# flight_computer.net
KiCad netlist of a schematic drawn in EAGLE
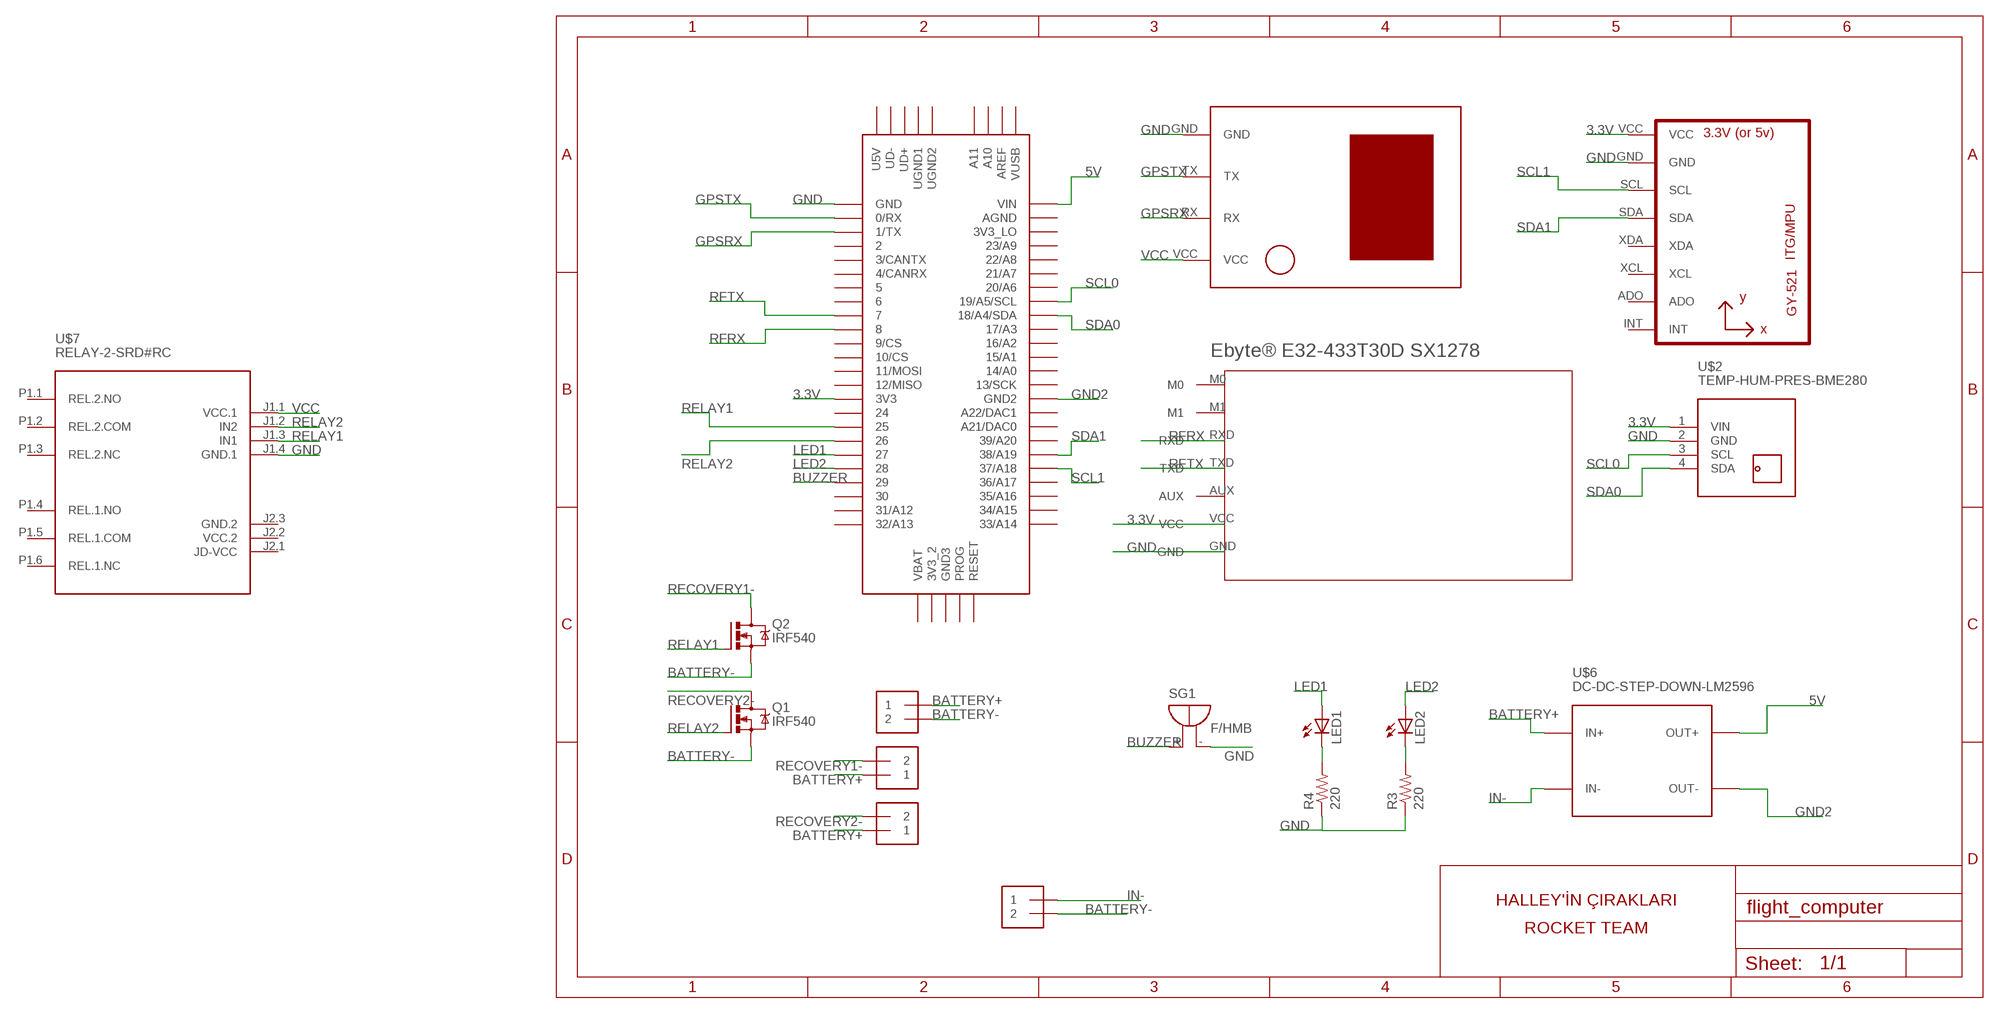
[diagram p0: schematic, sheet 1]

(export (version "E")
  (design (tool "Eeschema 10.0.6"))
  (components
    (comp (ref "J1")
      (value "1X2-3.5MM")
      (footprint "eagle-import:1X2-3.5MM")
      (libsource (lib "eagle-import") (part "1X2-3.5MM"))
    )
    (comp (ref "J2")
      (value "1X2-3.5MM")
      (footprint "eagle-import:1X2-3.5MM")
      (libsource (lib "eagle-import") (part "1X2-3.5MM"))
    )
    (comp (ref "J3")
      (value "1X2-3.5MM")
      (footprint "eagle-import:1X2-3.5MM")
      (libsource (lib "eagle-import") (part "1X2-3.5MM"))
    )
    (comp (ref "J4")
      (value "1X2-3.5MM")
      (footprint "eagle-import:1X2-3.5MM")
      (libsource (lib "eagle-import") (part "1X2-3.5MM"))
    )
    (comp (ref "LED1")
      (value "LED5MM")
      (footprint "eagle-import:LED5MM")
      (libsource (lib "eagle-import") (part "LED5MM"))
    )
    (comp (ref "LED2")
      (value "LED5MM")
      (footprint "eagle-import:LED5MM")
      (libsource (lib "eagle-import") (part "LED5MM"))
    )
    (comp (ref "Q1")
      (value "IRF540")
      (footprint "eagle-import:TO220BV")
      (fields (field (name "MANUFACTURER") "Infineon Technologies") (field (name "MPN") "IRF540NPBF"))
      (libsource (lib "eagle-import") (part "NMOSFET_-TO220IRF540"))
    )
    (comp (ref "Q2")
      (value "IRF540")
      (footprint "eagle-import:TO220BV")
      (fields (field (name "MANUFACTURER") "Infineon Technologies") (field (name "MPN") "IRF540NPBF"))
      (libsource (lib "eagle-import") (part "NMOSFET_-TO220IRF540"))
    )
    (comp (ref "R3")
      (value "220")
      (footprint "eagle-import:0204_7")
      (libsource (lib "eagle-import") (part "R-US_0204/7"))
    )
    (comp (ref "R4")
      (value "220")
      (footprint "eagle-import:0204_7")
      (libsource (lib "eagle-import") (part "R-US_0204/7"))
    )
    (comp (ref "SG1")
      (value "F/HMB")
      (footprint "eagle-import:F_HMB")
      (libsource (lib "eagle-import") (part "F/HMB"))
    )
    (comp (ref "U$1")
      (value "U-BLOX-NEO6V2")
      (footprint "eagle-import:U-BLOX-NEO6V2")
      (libsource (lib "eagle-import") (part "U-BLOX-NEO6V2"))
    )
    (comp (ref "U$2")
      (value "TEMP-HUM-PRES-BME280")
      (footprint "eagle-import:TEMP-HUM-PRES-BME280")
      (libsource (lib "eagle-import") (part "TEMP-HUM-PRES-BME280"))
    )
    (comp (ref "U$3")
      (value "TEENSY_3.5/3.6")
      (footprint "eagle-import:TEENSY_3.5_3.6")
      (libsource (lib "eagle-import") (part "TEENSY_3.5/3.6"))
    )
    (comp (ref "U$4")
      (value "EBYTE®E32-433T30DSX1278")
      (footprint "eagle-import:E32-433T30D")
      (libsource (lib "eagle-import") (part "EBYTE®E32-433T30DSX1278"))
    )
    (comp (ref "U$6")
      (value "DC-DC-STEP-DOWN-LM2596")
      (footprint "eagle-import:DC-DC-STEP-DOWN-LM2596")
      (libsource (lib "eagle-import") (part "DC-DC-STEP-DOWN-LM2596"))
    )
    (comp (ref "U$7")
      (value "RELAY-2-SRD#RC")
      (footprint "eagle-import:RELAY-2-SRD#RC")
      (libsource (lib "eagle-import") (part "RELAY-2-SRD#RC"))
    )
    (comp (ref "U1")
      (value "GY-521MPU6050")
      (footprint "eagle-import:GY-521")
      (libsource (lib "eagle-import") (part "GY-521MPU6050"))
    )
  )
  (nets
    (net (code "1") (name "/3.3V") (class "Default")
      (node (ref "U$2") (pin "1") (pinfunction "VIN_1") (pintype "power_in"))
      (node (ref "U$3") (pin "3V3") (pinfunction "3V3_3V3") (pintype "bidirectional"))
      (node (ref "U$4") (pin "VCC") (pinfunction "VCC_VCC") (pintype "bidirectional"))
      (node (ref "U1") (pin "VCC") (pinfunction "VCC_VCC") (pintype "bidirectional"))
    )
    (net (code "2") (name "/5V") (class "Default")
      (node (ref "U$3") (pin "VIN") (pinfunction "VIN_VIN") (pintype "bidirectional"))
      (node (ref "U$6") (pin "OUT+") (pinfunction "OUT+_OUT+") (pintype "bidirectional"))
    )
    (net (code "3") (name "/BATTERY+") (class "Default")
      (node (ref "J1") (pin "1") (pinfunction "1_1") (pintype "passive"))
      (node (ref "J2") (pin "1") (pinfunction "1_1") (pintype "passive"))
      (node (ref "J3") (pin "1") (pinfunction "1_1") (pintype "passive"))
      (node (ref "U$6") (pin "IN+") (pinfunction "IN+_IN+") (pintype "bidirectional"))
    )
    (net (code "4") (name "/BATTERY-") (class "Default")
      (node (ref "J1") (pin "2") (pinfunction "2_2") (pintype "passive"))
      (node (ref "J4") (pin "2") (pinfunction "2_2") (pintype "passive"))
      (node (ref "Q1") (pin "S") (pinfunction "S_S") (pintype "passive"))
      (node (ref "Q2") (pin "S") (pinfunction "S_S") (pintype "passive"))
    )
    (net (code "5") (name "/BUZZER") (class "Default")
      (node (ref "SG1") (pin "+") (pinfunction "+_+") (pintype "passive"))
      (node (ref "U$3") (pin "29") (pinfunction "29_29") (pintype "bidirectional"))
    )
    (net (code "6") (name "/GND") (class "Default")
      (node (ref "R3") (pin "1") (pinfunction "1_1") (pintype "passive"))
      (node (ref "R4") (pin "1") (pinfunction "1_1") (pintype "passive"))
      (node (ref "SG1") (pin "-") (pinfunction "-_-") (pintype "passive"))
      (node (ref "U$1") (pin "GND") (pinfunction "GND_GND") (pintype "bidirectional"))
      (node (ref "U$2") (pin "2") (pinfunction "GND_2") (pintype "power_in"))
      (node (ref "U$3") (pin "GND") (pinfunction "GND_GND") (pintype "bidirectional"))
      (node (ref "U$4") (pin "GND") (pinfunction "GND_GND") (pintype "bidirectional"))
      (node (ref "U$7") (pin "J1.4") (pinfunction "GND.1_J1.4") (pintype "power_in"))
      (node (ref "U1") (pin "GND") (pinfunction "GND_GND") (pintype "bidirectional"))
    )
    (net (code "7") (name "/GND.2") (class "Default")
      (node (ref "U$7") (pin "J2.3") (pinfunction "GND.2_J2.3") (pintype "power_in"))
    )
    (net (code "8") (name "/GND2") (class "Default")
      (node (ref "U$3") (pin "GND2") (pinfunction "GND2_GND2") (pintype "bidirectional"))
      (node (ref "U$6") (pin "OUT-") (pinfunction "OUT-_OUT-") (pintype "bidirectional"))
    )
    (net (code "9") (name "/GPSRX") (class "Default")
      (node (ref "U$1") (pin "RX") (pinfunction "RX_RX") (pintype "bidirectional"))
      (node (ref "U$3") (pin "1/TX") (pinfunction "1/TX_1/TX") (pintype "bidirectional"))
    )
    (net (code "10") (name "/GPSTX") (class "Default")
      (node (ref "U$1") (pin "TX") (pinfunction "TX_TX") (pintype "bidirectional"))
      (node (ref "U$3") (pin "0/RX") (pinfunction "0/RX_0/RX") (pintype "bidirectional"))
    )
    (net (code "11") (name "/IN-") (class "Default")
      (node (ref "J4") (pin "1") (pinfunction "1_1") (pintype "passive"))
      (node (ref "U$6") (pin "IN-") (pinfunction "IN-_IN-") (pintype "bidirectional"))
    )
    (net (code "12") (name "/LED1") (class "Default")
      (node (ref "LED1") (pin "A") (pinfunction "A_A") (pintype "passive"))
      (node (ref "U$3") (pin "27") (pinfunction "27_27") (pintype "bidirectional"))
    )
    (net (code "13") (name "/LED2") (class "Default")
      (node (ref "LED2") (pin "A") (pinfunction "A_A") (pintype "passive"))
      (node (ref "U$3") (pin "28") (pinfunction "28_28") (pintype "bidirectional"))
    )
    (net (code "14") (name "/RECOVERY1-") (class "Default")
      (node (ref "J2") (pin "2") (pinfunction "2_2") (pintype "passive"))
      (node (ref "Q2") (pin "D") (pinfunction "D_D") (pintype "passive"))
    )
    (net (code "15") (name "/RECOVERY2-") (class "Default")
      (node (ref "J3") (pin "2") (pinfunction "2_2") (pintype "passive"))
      (node (ref "Q1") (pin "D") (pinfunction "D_D") (pintype "passive"))
    )
    (net (code "16") (name "/RELAY1") (class "Default")
      (node (ref "Q2") (pin "G") (pinfunction "G_G") (pintype "passive"))
      (node (ref "U$3") (pin "25") (pinfunction "25_25") (pintype "bidirectional"))
      (node (ref "U$7") (pin "J1.3") (pinfunction "IN1_J1.3") (pintype "bidirectional"))
    )
    (net (code "17") (name "/RELAY2") (class "Default")
      (node (ref "Q1") (pin "G") (pinfunction "G_G") (pintype "passive"))
      (node (ref "U$3") (pin "26") (pinfunction "26_26") (pintype "bidirectional"))
      (node (ref "U$7") (pin "J1.2") (pinfunction "IN2_J1.2") (pintype "bidirectional"))
    )
    (net (code "18") (name "/RFRX") (class "Default")
      (node (ref "U$3") (pin "8") (pinfunction "8_8") (pintype "bidirectional"))
      (node (ref "U$4") (pin "RXD") (pinfunction "RXD_RXD") (pintype "bidirectional"))
    )
    (net (code "19") (name "/RFTX") (class "Default")
      (node (ref "U$3") (pin "7") (pinfunction "7_7") (pintype "bidirectional"))
      (node (ref "U$4") (pin "TXD") (pinfunction "TXD_TXD") (pintype "bidirectional"))
    )
    (net (code "20") (name "/SCL0") (class "Default")
      (node (ref "U$2") (pin "3") (pinfunction "SCL_3") (pintype "bidirectional"))
      (node (ref "U$3") (pin "19/A5/SCL") (pinfunction "19/A5/SCL_19/A5/SCL") (pintype "bidirectional"))
    )
    (net (code "21") (name "/SCL1") (class "Default")
      (node (ref "U$3") (pin "37/A18") (pinfunction "37/A18_37/A18") (pintype "bidirectional"))
      (node (ref "U1") (pin "SCL") (pinfunction "SCL_SCL") (pintype "bidirectional"))
    )
    (net (code "22") (name "/SDA0") (class "Default")
      (node (ref "U$2") (pin "4") (pinfunction "SDA_4") (pintype "bidirectional"))
      (node (ref "U$3") (pin "18/A4/SDA") (pinfunction "18/A4/SDA_18/A4/SDA") (pintype "bidirectional"))
    )
    (net (code "23") (name "/SDA1") (class "Default")
      (node (ref "U$3") (pin "38/A19") (pinfunction "38/A19_38/A19") (pintype "bidirectional"))
      (node (ref "U1") (pin "SDA") (pinfunction "SDA_SDA") (pintype "bidirectional"))
    )
    (net (code "24") (name "/VCC") (class "Default")
      (node (ref "U$1") (pin "VCC") (pinfunction "VCC_VCC") (pintype "bidirectional"))
      (node (ref "U$7") (pin "J1.1") (pinfunction "VCC.1_J1.1") (pintype "power_in"))
    )
    (net (code "25") (name "/VCC.2") (class "Default")
      (node (ref "U$7") (pin "J2.2") (pinfunction "VCC.2_J2.2") (pintype "power_in"))
    )
    (net (code "26") (name "Net-(LED1-C)") (class "Default")
      (node (ref "LED1") (pin "K") (pinfunction "C_K") (pintype "passive"))
      (node (ref "R4") (pin "2") (pinfunction "2_2") (pintype "passive"))
    )
    (net (code "27") (name "Net-(LED2-C)") (class "Default")
      (node (ref "LED2") (pin "K") (pinfunction "C_K") (pintype "passive"))
      (node (ref "R3") (pin "2") (pinfunction "2_2") (pintype "passive"))
    )
    (net (code "28") (name "unconnected-(U$3-A21{slash}DAC0-Pad21{slash}DAC0)") (class "Default")
      (node (ref "U$3") (pin "21/DAC0") (pinfunction "A21/DAC0_21/DAC0") (pintype "bidirectional"))
    )
    (net (code "29") (name "unconnected-(U$3-Pad2)") (class "Default")
      (node (ref "U$3") (pin "2") (pinfunction "2_2") (pintype "bidirectional"))
    )
    (net (code "30") (name "unconnected-(U$3-Pad3V3_2)") (class "Default")
      (node (ref "U$3") (pin "3V3_2") (pinfunction "3V3_2_3V3_2") (pintype "bidirectional"))
    )
    (net (code "31") (name "unconnected-(U$3-Pad3V3_LO)") (class "Default")
      (node (ref "U$3") (pin "3V3_LO") (pinfunction "3V3_LO_3V3_LO") (pintype "bidirectional"))
    )
    (net (code "32") (name "unconnected-(U$3-Pad3{slash}CANTX)") (class "Default")
      (node (ref "U$3") (pin "3/CANTX") (pinfunction "3/CANTX_3/CANTX") (pintype "bidirectional"))
    )
    (net (code "33") (name "unconnected-(U$3-Pad4{slash}CANRX)") (class "Default")
      (node (ref "U$3") (pin "4/CANRX") (pinfunction "4/CANRX_4/CANRX") (pintype "bidirectional"))
    )
    (net (code "34") (name "unconnected-(U$3-Pad5)") (class "Default")
      (node (ref "U$3") (pin "5") (pinfunction "5_5") (pintype "bidirectional"))
    )
    (net (code "35") (name "unconnected-(U$3-Pad6)") (class "Default")
      (node (ref "U$3") (pin "6") (pinfunction "6_6") (pintype "bidirectional"))
    )
    (net (code "36") (name "unconnected-(U$3-Pad9{slash}CS)") (class "Default")
      (node (ref "U$3") (pin "9/CS") (pinfunction "9/CS_9/CS") (pintype "bidirectional"))
    )
    (net (code "37") (name "unconnected-(U$3-Pad10{slash}CS)") (class "Default")
      (node (ref "U$3") (pin "10/CS") (pinfunction "10/CS_10/CS") (pintype "bidirectional"))
    )
    (net (code "38") (name "unconnected-(U$3-Pad11{slash}MOSI)") (class "Default")
      (node (ref "U$3") (pin "11/MOSI") (pinfunction "11/MOSI_11/MOSI") (pintype "bidirectional"))
    )
    (net (code "39") (name "unconnected-(U$3-Pad12{slash}MISO)") (class "Default")
      (node (ref "U$3") (pin "12/MISO") (pinfunction "12/MISO_12/MISO") (pintype "bidirectional"))
    )
    (net (code "40") (name "unconnected-(U$3-Pad13{slash}SCK)") (class "Default")
      (node (ref "U$3") (pin "13/SCK") (pinfunction "13/SCK_13/SCK") (pintype "bidirectional"))
    )
    (net (code "41") (name "unconnected-(U$3-Pad14{slash}A0)") (class "Default")
      (node (ref "U$3") (pin "14/A0") (pinfunction "14/A0_14/A0") (pintype "bidirectional"))
    )
    (net (code "42") (name "unconnected-(U$3-Pad15{slash}A1)") (class "Default")
      (node (ref "U$3") (pin "15/A1") (pinfunction "15/A1_15/A1") (pintype "bidirectional"))
    )
    (net (code "43") (name "unconnected-(U$3-Pad16{slash}A2)") (class "Default")
      (node (ref "U$3") (pin "16/A2") (pinfunction "16/A2_16/A2") (pintype "bidirectional"))
    )
    (net (code "44") (name "unconnected-(U$3-Pad17{slash}A3)") (class "Default")
      (node (ref "U$3") (pin "17/A3") (pinfunction "17/A3_17/A3") (pintype "bidirectional"))
    )
    (net (code "45") (name "unconnected-(U$3-Pad20{slash}A6)") (class "Default")
      (node (ref "U$3") (pin "20/A6") (pinfunction "20/A6_20/A6") (pintype "bidirectional"))
    )
    (net (code "46") (name "unconnected-(U$3-Pad21{slash}A7)") (class "Default")
      (node (ref "U$3") (pin "21/A7") (pinfunction "21/A7_21/A7") (pintype "bidirectional"))
    )
    (net (code "47") (name "unconnected-(U$3-Pad22{slash}A8)") (class "Default")
      (node (ref "U$3") (pin "22/A8") (pinfunction "22/A8_22/A8") (pintype "bidirectional"))
    )
    (net (code "48") (name "unconnected-(U$3-Pad23{slash}A9)") (class "Default")
      (node (ref "U$3") (pin "23/A9") (pinfunction "23/A9_23/A9") (pintype "bidirectional"))
    )
    (net (code "49") (name "unconnected-(U$3-Pad24)") (class "Default")
      (node (ref "U$3") (pin "24") (pinfunction "24_24") (pintype "bidirectional"))
    )
    (net (code "50") (name "unconnected-(U$3-Pad30)") (class "Default")
      (node (ref "U$3") (pin "30") (pinfunction "30_30") (pintype "bidirectional"))
    )
    (net (code "51") (name "unconnected-(U$3-Pad31{slash}A12)") (class "Default")
      (node (ref "U$3") (pin "31/A12") (pinfunction "31/A12_31/A12") (pintype "bidirectional"))
    )
    (net (code "52") (name "unconnected-(U$3-Pad32{slash}A13)") (class "Default")
      (node (ref "U$3") (pin "32/A13") (pinfunction "32/A13_32/A13") (pintype "bidirectional"))
    )
    (net (code "53") (name "unconnected-(U$3-Pad33{slash}A14)") (class "Default")
      (node (ref "U$3") (pin "33/A14") (pinfunction "33/A14_33/A14") (pintype "bidirectional"))
    )
    (net (code "54") (name "unconnected-(U$3-Pad34{slash}A15)") (class "Default")
      (node (ref "U$3") (pin "34/A15") (pinfunction "34/A15_34/A15") (pintype "bidirectional"))
    )
    (net (code "55") (name "unconnected-(U$3-Pad35{slash}A16)") (class "Default")
      (node (ref "U$3") (pin "35/A16") (pinfunction "35/A16_35/A16") (pintype "bidirectional"))
    )
    (net (code "56") (name "unconnected-(U$3-Pad36{slash}A17)") (class "Default")
      (node (ref "U$3") (pin "36/A17") (pinfunction "36/A17_36/A17") (pintype "bidirectional"))
    )
    (net (code "57") (name "unconnected-(U$3-Pad39{slash}A20)") (class "Default")
      (node (ref "U$3") (pin "39/A20") (pinfunction "39/A20_39/A20") (pintype "bidirectional"))
    )
    (net (code "58") (name "unconnected-(U$3-PadA10)") (class "Default")
      (node (ref "U$3") (pin "A10") (pinfunction "A10_A10") (pintype "bidirectional"))
    )
    (net (code "59") (name "unconnected-(U$3-PadA11)") (class "Default")
      (node (ref "U$3") (pin "A11") (pinfunction "A11_A11") (pintype "bidirectional"))
    )
    (net (code "60") (name "unconnected-(U$3-PadA22{slash}DAC1)") (class "Default")
      (node (ref "U$3") (pin "A22/DAC1") (pinfunction "A22/DAC1_A22/DAC1") (pintype "bidirectional"))
    )
    (net (code "61") (name "unconnected-(U$3-PadAGND)") (class "Default")
      (node (ref "U$3") (pin "AGND") (pinfunction "AGND_AGND") (pintype "bidirectional"))
    )
    (net (code "62") (name "unconnected-(U$3-PadAREF)") (class "Default")
      (node (ref "U$3") (pin "AREF") (pinfunction "AREF_AREF") (pintype "bidirectional"))
    )
    (net (code "63") (name "unconnected-(U$3-PadGND3)") (class "Default")
      (node (ref "U$3") (pin "GND3") (pinfunction "GND3_GND3") (pintype "bidirectional"))
    )
    (net (code "64") (name "unconnected-(U$3-PadPROG)") (class "Default")
      (node (ref "U$3") (pin "PROG") (pinfunction "PROG_PROG") (pintype "bidirectional"))
    )
    (net (code "65") (name "unconnected-(U$3-PadRESET)") (class "Default")
      (node (ref "U$3") (pin "RESET") (pinfunction "RESET_RESET") (pintype "bidirectional"))
    )
    (net (code "66") (name "unconnected-(U$3-PadU5V)") (class "Default")
      (node (ref "U$3") (pin "U5V") (pinfunction "U5V_U5V") (pintype "bidirectional"))
    )
    (net (code "67") (name "unconnected-(U$3-PadUD+)") (class "Default")
      (node (ref "U$3") (pin "UD+") (pinfunction "UD+_UD+") (pintype "bidirectional"))
    )
    (net (code "68") (name "unconnected-(U$3-PadUD-)") (class "Default")
      (node (ref "U$3") (pin "UD-") (pinfunction "UD-_UD-") (pintype "bidirectional"))
    )
    (net (code "69") (name "unconnected-(U$3-PadUGND1)") (class "Default")
      (node (ref "U$3") (pin "UGND1") (pinfunction "UGND1_UGND1") (pintype "bidirectional"))
    )
    (net (code "70") (name "unconnected-(U$3-PadUGND2)") (class "Default")
      (node (ref "U$3") (pin "UGND2") (pinfunction "UGND2_UGND2") (pintype "bidirectional"))
    )
    (net (code "71") (name "unconnected-(U$3-PadVBAT)") (class "Default")
      (node (ref "U$3") (pin "VBAT") (pinfunction "VBAT_VBAT") (pintype "bidirectional"))
    )
    (net (code "72") (name "unconnected-(U$3-PadVUSB)") (class "Default")
      (node (ref "U$3") (pin "VUSB") (pinfunction "VUSB_VUSB") (pintype "bidirectional"))
    )
    (net (code "73") (name "unconnected-(U$4-PadAUX)") (class "Default")
      (node (ref "U$4") (pin "AUX") (pinfunction "AUX_AUX") (pintype "bidirectional"))
    )
    (net (code "74") (name "unconnected-(U$4-PadM0)") (class "Default")
      (node (ref "U$4") (pin "M0") (pinfunction "M0_M0") (pintype "bidirectional"))
    )
    (net (code "75") (name "unconnected-(U$4-PadM1)") (class "Default")
      (node (ref "U$4") (pin "M1") (pinfunction "M1_M1") (pintype "bidirectional"))
    )
    (net (code "76") (name "unconnected-(U$7-JD-VCC-PadJ2.1)") (class "Default")
      (node (ref "U$7") (pin "J2.1") (pinfunction "JD-VCC_J2.1") (pintype "bidirectional"))
    )
    (net (code "77") (name "unconnected-(U$7-REL.1.COM-PadP1.5)") (class "Default")
      (node (ref "U$7") (pin "P1.5") (pinfunction "REL.1.COM_P1.5") (pintype "bidirectional"))
    )
    (net (code "78") (name "unconnected-(U$7-REL.1.NC-PadP1.6)") (class "Default")
      (node (ref "U$7") (pin "P1.6") (pinfunction "REL.1.NC_P1.6") (pintype "bidirectional"))
    )
    (net (code "79") (name "unconnected-(U$7-REL.1.NO-PadP1.4)") (class "Default")
      (node (ref "U$7") (pin "P1.4") (pinfunction "REL.1.NO_P1.4") (pintype "bidirectional"))
    )
    (net (code "80") (name "unconnected-(U$7-REL.2.COM-PadP1.2)") (class "Default")
      (node (ref "U$7") (pin "P1.2") (pinfunction "REL.2.COM_P1.2") (pintype "bidirectional"))
    )
    (net (code "81") (name "unconnected-(U$7-REL.2.NC-PadP1.3)") (class "Default")
      (node (ref "U$7") (pin "P1.3") (pinfunction "REL.2.NC_P1.3") (pintype "bidirectional"))
    )
    (net (code "82") (name "unconnected-(U$7-REL.2.NO-PadP1.1)") (class "Default")
      (node (ref "U$7") (pin "P1.1") (pinfunction "REL.2.NO_P1.1") (pintype "bidirectional"))
    )
    (net (code "83") (name "unconnected-(U1-PadADO)") (class "Default")
      (node (ref "U1") (pin "ADO") (pinfunction "ADO_ADO") (pintype "bidirectional"))
    )
    (net (code "84") (name "unconnected-(U1-PadINT)") (class "Default")
      (node (ref "U1") (pin "INT") (pinfunction "INT_INT") (pintype "bidirectional"))
    )
    (net (code "85") (name "unconnected-(U1-PadXCL)") (class "Default")
      (node (ref "U1") (pin "XCL") (pinfunction "XCL_XCL") (pintype "bidirectional"))
    )
    (net (code "86") (name "unconnected-(U1-PadXDA)") (class "Default")
      (node (ref "U1") (pin "XDA") (pinfunction "XDA_XDA") (pintype "bidirectional"))
    )
  )
)
